# ArduinoBuzzerLed.net
KiCad netlist of a schematic drawn in EAGLE
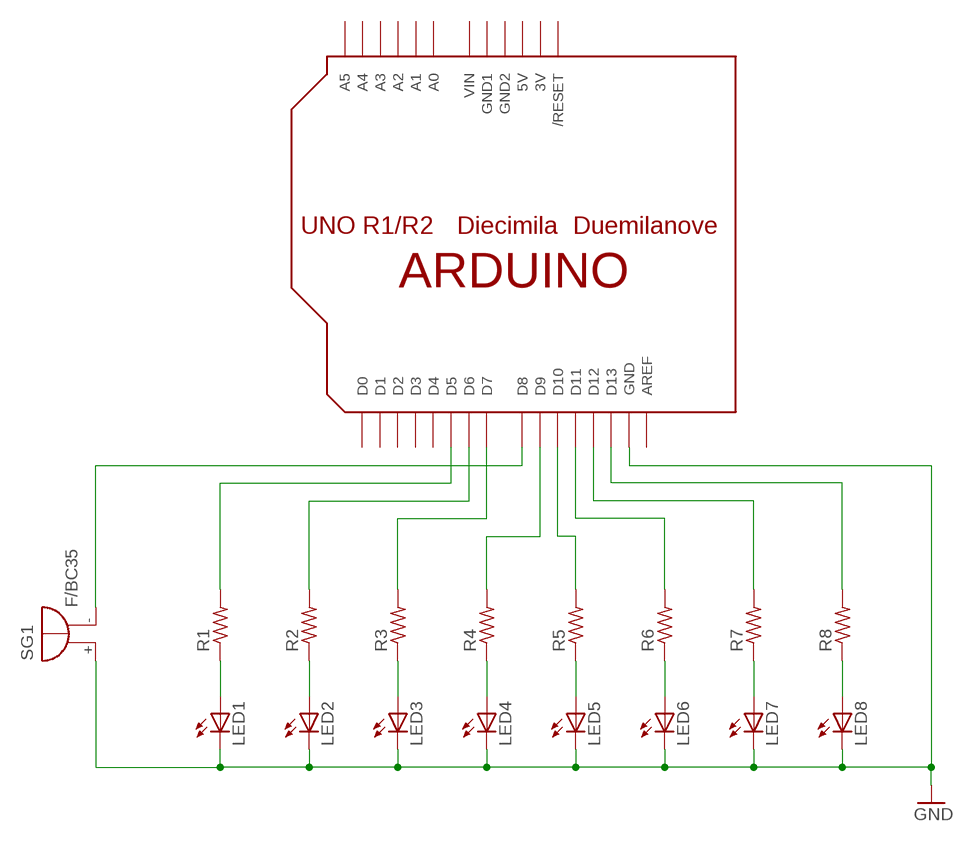
[diagram p0: schematic, sheet 1]

(export (version "E")
  (design (tool "Eeschema 10.0.6"))
  (components
    (comp (ref "LED1")
      (value "LED5MM")
      (footprint "eagle-import:LED5MM")
      (libsource (lib "eagle-import") (part "LED5MM"))
    )
    (comp (ref "LED2")
      (value "LED5MM")
      (footprint "eagle-import:LED5MM")
      (libsource (lib "eagle-import") (part "LED5MM"))
    )
    (comp (ref "LED3")
      (value "LED5MM")
      (footprint "eagle-import:LED5MM")
      (libsource (lib "eagle-import") (part "LED5MM"))
    )
    (comp (ref "LED4")
      (value "LED5MM")
      (footprint "eagle-import:LED5MM")
      (libsource (lib "eagle-import") (part "LED5MM"))
    )
    (comp (ref "LED5")
      (value "LED5MM")
      (footprint "eagle-import:LED5MM")
      (libsource (lib "eagle-import") (part "LED5MM"))
    )
    (comp (ref "LED6")
      (value "LED5MM")
      (footprint "eagle-import:LED5MM")
      (libsource (lib "eagle-import") (part "LED5MM"))
    )
    (comp (ref "LED7")
      (value "LED5MM")
      (footprint "eagle-import:LED5MM")
      (libsource (lib "eagle-import") (part "LED5MM"))
    )
    (comp (ref "LED8")
      (value "LED5MM")
      (footprint "eagle-import:LED5MM")
      (libsource (lib "eagle-import") (part "LED5MM"))
    )
    (comp (ref "R1")
      (value "R-US_0204/7")
      (footprint "eagle-import:0204_7")
      (libsource (lib "eagle-import") (part "R-US_0204/7"))
    )
    (comp (ref "R2")
      (value "R-US_0204/7")
      (footprint "eagle-import:0204_7")
      (libsource (lib "eagle-import") (part "R-US_0204/7"))
    )
    (comp (ref "R3")
      (value "R-US_0204/7")
      (footprint "eagle-import:0204_7")
      (libsource (lib "eagle-import") (part "R-US_0204/7"))
    )
    (comp (ref "R4")
      (value "R-US_0204/7")
      (footprint "eagle-import:0204_7")
      (libsource (lib "eagle-import") (part "R-US_0204/7"))
    )
    (comp (ref "R5")
      (value "R-US_0204/7")
      (footprint "eagle-import:0204_7")
      (libsource (lib "eagle-import") (part "R-US_0204/7"))
    )
    (comp (ref "R6")
      (value "R-US_0204/7")
      (footprint "eagle-import:0204_7")
      (libsource (lib "eagle-import") (part "R-US_0204/7"))
    )
    (comp (ref "R7")
      (value "R-US_0204/7")
      (footprint "eagle-import:0204_7")
      (libsource (lib "eagle-import") (part "R-US_0204/7"))
    )
    (comp (ref "R8")
      (value "R-US_0204/7")
      (footprint "eagle-import:0204_7")
      (libsource (lib "eagle-import") (part "R-US_0204/7"))
    )
    (comp (ref "SG1")
      (value "F/BC35")
      (footprint "eagle-import:F_BC35")
      (libsource (lib "eagle-import") (part "F/BC35"))
    )
    (comp (ref "U$2")
      (value "ARDUINOUNO")
      (footprint "eagle-import:ARDUINO")
      (libsource (lib "eagle-import") (part "ARDUINOUNO"))
    )
  )
  (nets
    (net (code "1") (name "/3V") (class "Default")
      (node (ref "U$2") (pin "3V") (pinfunction "3V_3V") (pintype "power_in"))
    )
    (net (code "2") (name "/5V") (class "Default")
      (node (ref "U$2") (pin "5V") (pinfunction "5V_5V") (pintype "power_in"))
    )
    (net (code "3") (name "/GND1") (class "Default")
      (node (ref "U$2") (pin "GND1") (pinfunction "GND1_GND1") (pintype "power_in"))
    )
    (net (code "4") (name "/GND2") (class "Default")
      (node (ref "U$2") (pin "GND2") (pinfunction "GND2_GND2") (pintype "power_in"))
    )
    (net (code "5") (name "/VIN") (class "Default")
      (node (ref "U$2") (pin "VIN") (pinfunction "VIN_VIN") (pintype "power_in"))
    )
    (net (code "6") (name "GND") (class "Default")
      (node (ref "LED1") (pin "K") (pinfunction "C_K") (pintype "passive"))
      (node (ref "LED2") (pin "K") (pinfunction "C_K") (pintype "passive"))
      (node (ref "LED3") (pin "K") (pinfunction "C_K") (pintype "passive"))
      (node (ref "LED4") (pin "K") (pinfunction "C_K") (pintype "passive"))
      (node (ref "LED5") (pin "K") (pinfunction "C_K") (pintype "passive"))
      (node (ref "LED6") (pin "K") (pinfunction "C_K") (pintype "passive"))
      (node (ref "LED7") (pin "K") (pinfunction "C_K") (pintype "passive"))
      (node (ref "LED8") (pin "K") (pinfunction "C_K") (pintype "passive"))
      (node (ref "SG1") (pin "+") (pinfunction "+_+") (pintype "passive"))
      (node (ref "U$2") (pin "GND") (pinfunction "GND_GND") (pintype "power_in"))
    )
    (net (code "7") (name "Net-(LED1-PadA)") (class "Default")
      (node (ref "LED1") (pin "A") (pinfunction "A_A") (pintype "passive"))
      (node (ref "R1") (pin "1") (pinfunction "1_1") (pintype "passive"))
    )
    (net (code "8") (name "Net-(LED2-PadA)") (class "Default")
      (node (ref "LED2") (pin "A") (pinfunction "A_A") (pintype "passive"))
      (node (ref "R2") (pin "1") (pinfunction "1_1") (pintype "passive"))
    )
    (net (code "9") (name "Net-(LED3-PadA)") (class "Default")
      (node (ref "LED3") (pin "A") (pinfunction "A_A") (pintype "passive"))
      (node (ref "R3") (pin "1") (pinfunction "1_1") (pintype "passive"))
    )
    (net (code "10") (name "Net-(LED4-PadA)") (class "Default")
      (node (ref "LED4") (pin "A") (pinfunction "A_A") (pintype "passive"))
      (node (ref "R4") (pin "1") (pinfunction "1_1") (pintype "passive"))
    )
    (net (code "11") (name "Net-(LED5-PadA)") (class "Default")
      (node (ref "LED5") (pin "A") (pinfunction "A_A") (pintype "passive"))
      (node (ref "R5") (pin "1") (pinfunction "1_1") (pintype "passive"))
    )
    (net (code "12") (name "Net-(LED6-PadA)") (class "Default")
      (node (ref "LED6") (pin "A") (pinfunction "A_A") (pintype "passive"))
      (node (ref "R6") (pin "1") (pinfunction "1_1") (pintype "passive"))
    )
    (net (code "13") (name "Net-(LED7-PadA)") (class "Default")
      (node (ref "LED7") (pin "A") (pinfunction "A_A") (pintype "passive"))
      (node (ref "R7") (pin "1") (pinfunction "1_1") (pintype "passive"))
    )
    (net (code "14") (name "Net-(LED8-PadA)") (class "Default")
      (node (ref "LED8") (pin "A") (pinfunction "A_A") (pintype "passive"))
      (node (ref "R8") (pin "1") (pinfunction "1_1") (pintype "passive"))
    )
    (net (code "15") (name "Net-(R1-Pad2)") (class "Default")
      (node (ref "R1") (pin "2") (pinfunction "2_2") (pintype "passive"))
      (node (ref "U$2") (pin "D5") (pinfunction "D5_D5") (pintype "bidirectional"))
    )
    (net (code "16") (name "Net-(R2-Pad2)") (class "Default")
      (node (ref "R2") (pin "2") (pinfunction "2_2") (pintype "passive"))
      (node (ref "U$2") (pin "D6") (pinfunction "D6_D6") (pintype "bidirectional"))
    )
    (net (code "17") (name "Net-(R3-Pad2)") (class "Default")
      (node (ref "R3") (pin "2") (pinfunction "2_2") (pintype "passive"))
      (node (ref "U$2") (pin "D7") (pinfunction "D7_D7") (pintype "bidirectional"))
    )
    (net (code "18") (name "Net-(R4-Pad2)") (class "Default")
      (node (ref "R4") (pin "2") (pinfunction "2_2") (pintype "passive"))
      (node (ref "U$2") (pin "D9") (pinfunction "D9_D9") (pintype "bidirectional"))
    )
    (net (code "19") (name "Net-(R5-Pad2)") (class "Default")
      (node (ref "R5") (pin "2") (pinfunction "2_2") (pintype "passive"))
      (node (ref "U$2") (pin "D10") (pinfunction "D10_D10") (pintype "bidirectional"))
    )
    (net (code "20") (name "Net-(R6-Pad2)") (class "Default")
      (node (ref "R6") (pin "2") (pinfunction "2_2") (pintype "passive"))
      (node (ref "U$2") (pin "D11") (pinfunction "D11_D11") (pintype "bidirectional"))
    )
    (net (code "21") (name "Net-(R7-Pad2)") (class "Default")
      (node (ref "R7") (pin "2") (pinfunction "2_2") (pintype "passive"))
      (node (ref "U$2") (pin "D12") (pinfunction "D12_D12") (pintype "bidirectional"))
    )
    (net (code "22") (name "Net-(R8-Pad2)") (class "Default")
      (node (ref "R8") (pin "2") (pinfunction "2_2") (pintype "passive"))
      (node (ref "U$2") (pin "D13") (pinfunction "D13_D13") (pintype "bidirectional"))
    )
    (net (code "23") (name "Net-(SG1-Pad-)") (class "Default")
      (node (ref "SG1") (pin "-") (pinfunction "-_-") (pintype "passive"))
      (node (ref "U$2") (pin "D8") (pinfunction "D8_D8") (pintype "bidirectional"))
    )
    (net (code "24") (name "unconnected-(U$2-PadA0)") (class "Default")
      (node (ref "U$2") (pin "A0") (pinfunction "A0_A0") (pintype "bidirectional"))
    )
    (net (code "25") (name "unconnected-(U$2-PadA1)") (class "Default")
      (node (ref "U$2") (pin "A1") (pinfunction "A1_A1") (pintype "bidirectional"))
    )
    (net (code "26") (name "unconnected-(U$2-PadA2)") (class "Default")
      (node (ref "U$2") (pin "A2") (pinfunction "A2_A2") (pintype "bidirectional"))
    )
    (net (code "27") (name "unconnected-(U$2-PadA3)") (class "Default")
      (node (ref "U$2") (pin "A3") (pinfunction "A3_A3") (pintype "bidirectional"))
    )
    (net (code "28") (name "unconnected-(U$2-PadA4)") (class "Default")
      (node (ref "U$2") (pin "A4") (pinfunction "A4_A4") (pintype "bidirectional"))
    )
    (net (code "29") (name "unconnected-(U$2-PadA5)") (class "Default")
      (node (ref "U$2") (pin "A5") (pinfunction "A5_A5") (pintype "bidirectional"))
    )
    (net (code "30") (name "unconnected-(U$2-PadAREF)") (class "Default")
      (node (ref "U$2") (pin "AREF") (pinfunction "AREF_AREF") (pintype "bidirectional"))
    )
    (net (code "31") (name "unconnected-(U$2-PadD0)") (class "Default")
      (node (ref "U$2") (pin "D0") (pinfunction "D0_D0") (pintype "bidirectional"))
    )
    (net (code "32") (name "unconnected-(U$2-PadD1)") (class "Default")
      (node (ref "U$2") (pin "D1") (pinfunction "D1_D1") (pintype "bidirectional"))
    )
    (net (code "33") (name "unconnected-(U$2-PadD2)") (class "Default")
      (node (ref "U$2") (pin "D2") (pinfunction "D2_D2") (pintype "bidirectional"))
    )
    (net (code "34") (name "unconnected-(U$2-PadD3)") (class "Default")
      (node (ref "U$2") (pin "D3") (pinfunction "D3_D3") (pintype "bidirectional"))
    )
    (net (code "35") (name "unconnected-(U$2-PadD4)") (class "Default")
      (node (ref "U$2") (pin "D4") (pinfunction "D4_D4") (pintype "bidirectional"))
    )
    (net (code "36") (name "unconnected-(U$2-{slash}RESET-PadRESET)") (class "Default")
      (node (ref "U$2") (pin "RESET") (pinfunction "/RESET_RESET") (pintype "bidirectional"))
    )
  )
)
